# BackPlane4.net
KiCad netlist of a schematic drawn in Altium Designer
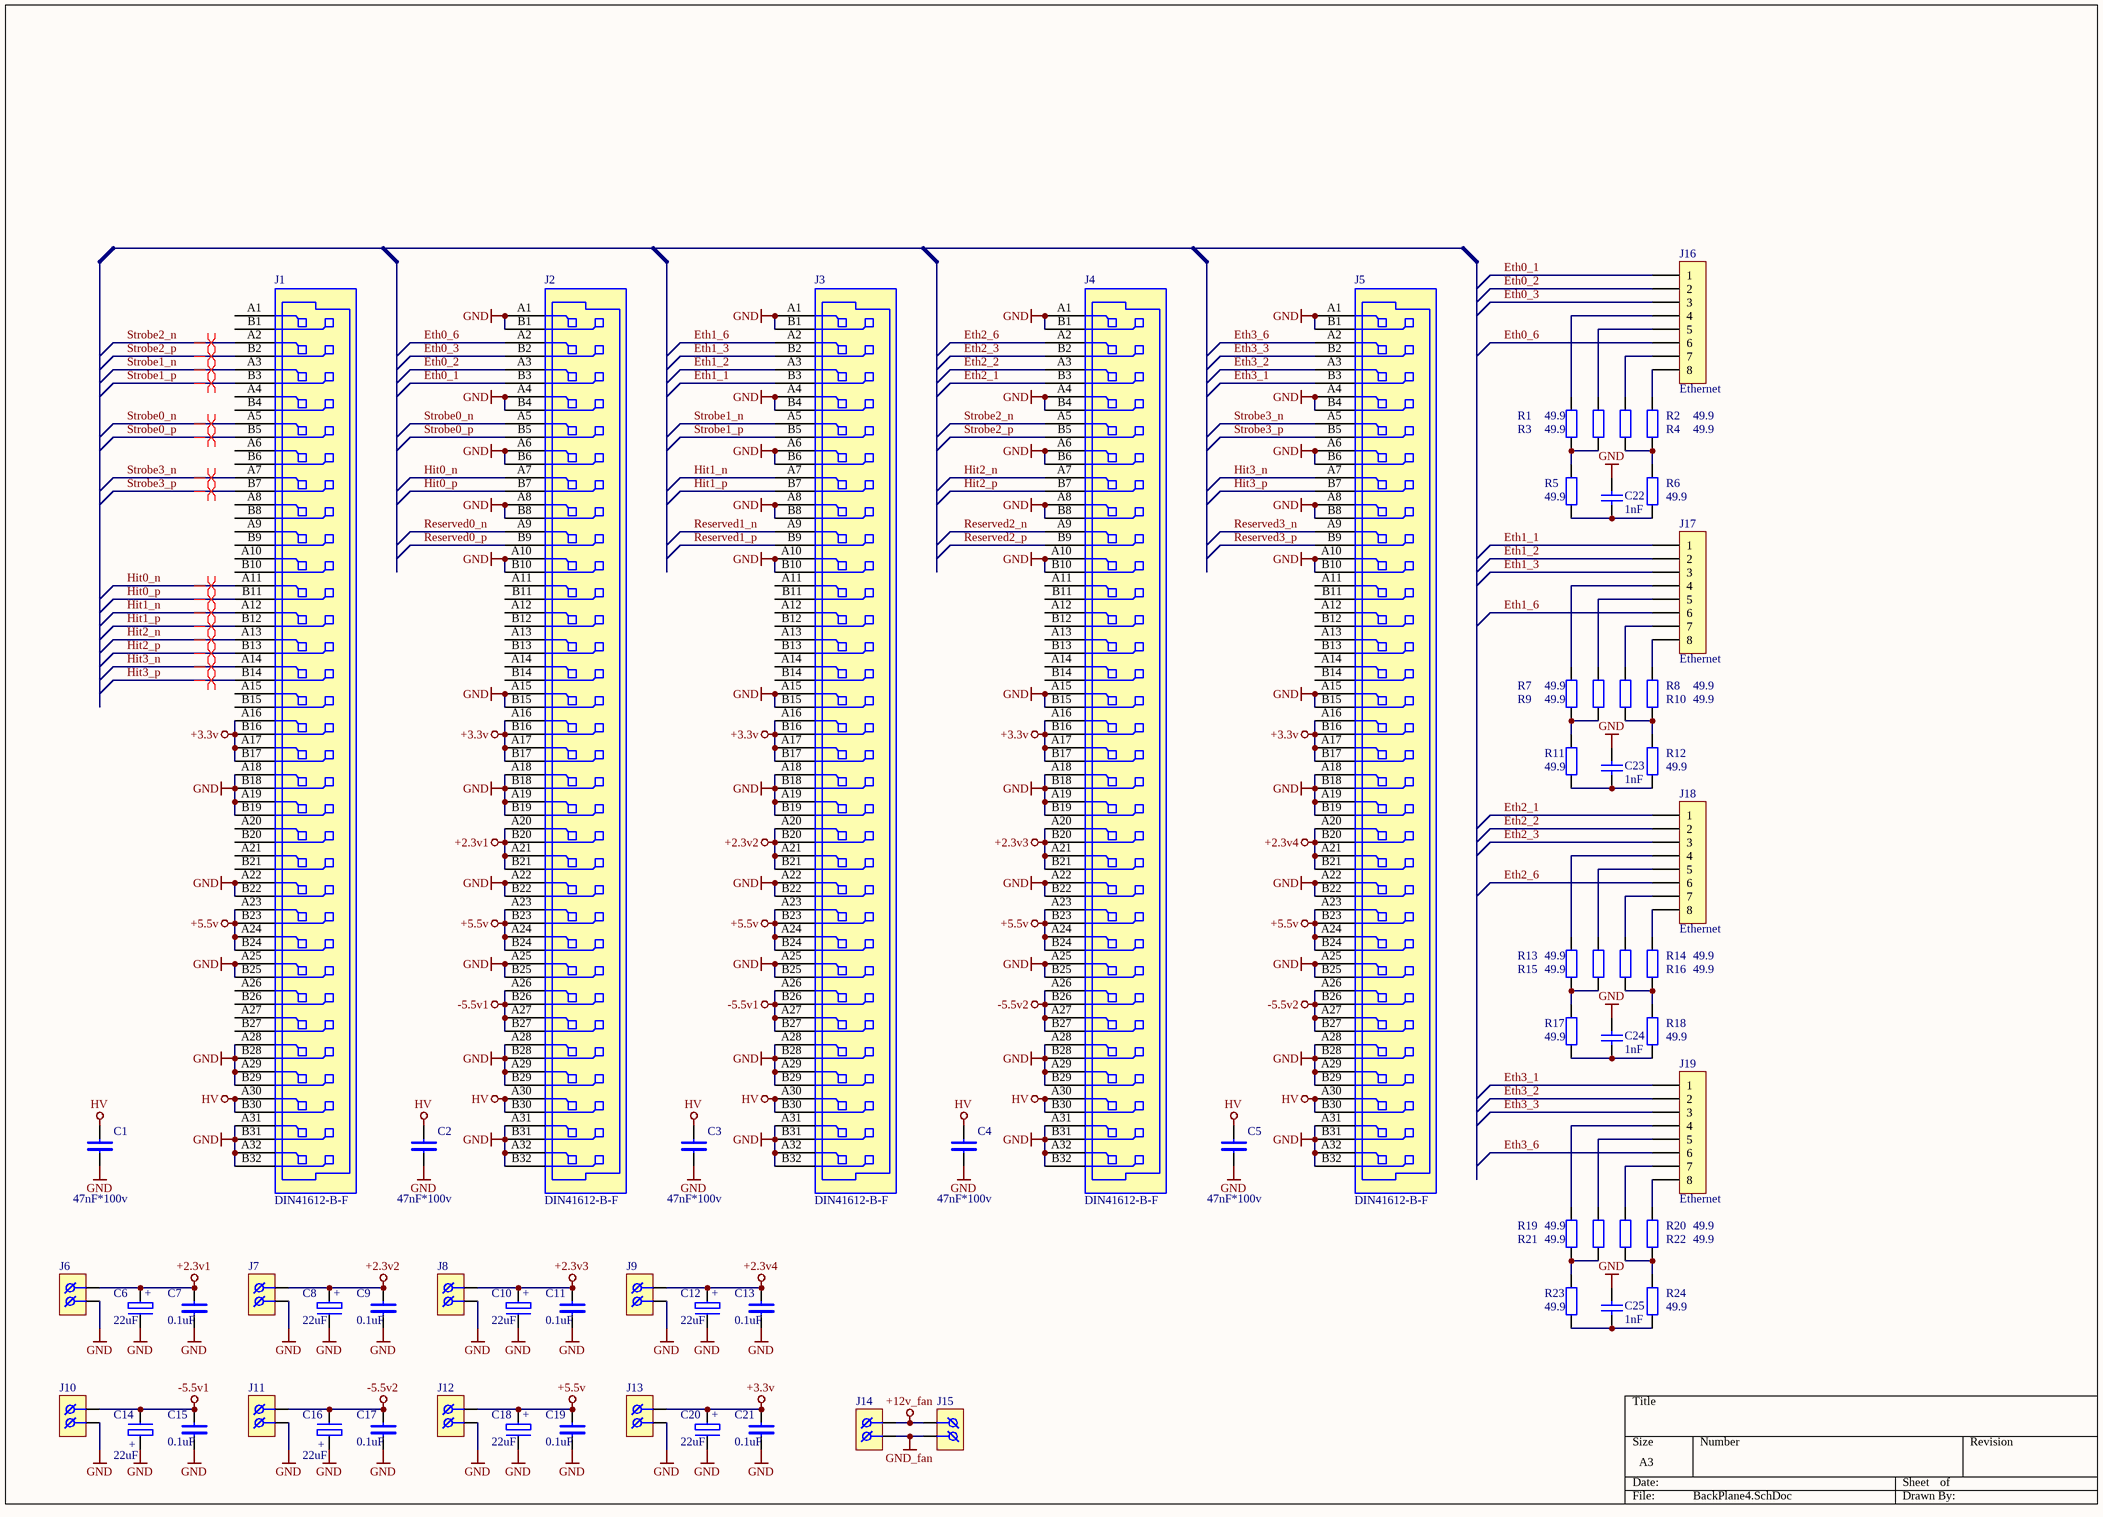
[diagram p0: BackPlane4.SchDoc]

(export (version "E")
  (design (tool "Eeschema 10.0.6"))
  (components
    (comp (ref "C1") (value "47nF*100v") (footprint "1206") (libsource (lib "*") (part "C")))
    (comp (ref "C2") (value "47nF*100v") (footprint "1206") (libsource (lib "*") (part "C")))
    (comp (ref "C3") (value "47nF*100v") (footprint "1206") (libsource (lib "*") (part "C")))
    (comp (ref "C4") (value "47nF*100v") (footprint "1206") (libsource (lib "*") (part "C")))
    (comp (ref "C5") (value "47nF*100v") (footprint "1206") (libsource (lib "*") (part "C")))
    (comp (ref "C6") (value "22uF") (footprint "CP6032") (libsource (lib "*") (part "C POL")))
    (comp (ref "C7") (value "0.1uF") (footprint "1206") (libsource (lib "*") (part "C")))
    (comp (ref "C8") (value "22uF") (footprint "CP6032") (libsource (lib "*") (part "C POL")))
    (comp (ref "C9") (value "0.1uF") (footprint "1206") (libsource (lib "*") (part "C")))
    (comp (ref "C10") (value "22uF") (footprint "CP6032") (libsource (lib "*") (part "C POL")))
    (comp (ref "C11") (value "0.1uF") (footprint "1206") (libsource (lib "*") (part "C")))
    (comp (ref "C12") (value "22uF") (footprint "CP6032") (libsource (lib "*") (part "C POL")))
    (comp (ref "C13") (value "0.1uF") (footprint "1206") (libsource (lib "*") (part "C")))
    (comp (ref "C14") (value "22uF") (footprint "CP6032") (libsource (lib "*") (part "C POL")))
    (comp (ref "C15") (value "0.1uF") (footprint "1206") (libsource (lib "*") (part "C")))
    (comp (ref "C16") (value "22uF") (footprint "CP6032") (libsource (lib "*") (part "C POL")))
    (comp (ref "C17") (value "0.1uF") (footprint "1206") (libsource (lib "*") (part "C")))
    (comp (ref "C18") (value "22uF") (footprint "CP6032") (libsource (lib "*") (part "C POL")))
    (comp (ref "C19") (value "0.1uF") (footprint "1206") (libsource (lib "*") (part "C")))
    (comp (ref "C20") (value "22uF") (footprint "CP6032") (libsource (lib "*") (part "C POL")))
    (comp (ref "C21") (value "0.1uF") (footprint "1206") (libsource (lib "*") (part "C")))
    (comp (ref "C22")
      (value "1nF")
      (footprint "0805")
      (description "Capacitor")
      (fields (field (name "PUBLISHER") "Altium Limited"))
      (libsource (lib "pcblib1") (part "Cap"))
    )
    (comp (ref "C23")
      (value "1nF")
      (footprint "0805")
      (description "Capacitor")
      (fields (field (name "PUBLISHER") "Altium Limited"))
      (libsource (lib "pcblib1") (part "Cap"))
    )
    (comp (ref "C24")
      (value "1nF")
      (footprint "0805")
      (description "Capacitor")
      (fields (field (name "PUBLISHER") "Altium Limited"))
      (libsource (lib "pcblib1") (part "Cap"))
    )
    (comp (ref "C25")
      (value "1nF")
      (footprint "0805")
      (description "Capacitor")
      (fields (field (name "PUBLISHER") "Altium Limited"))
      (libsource (lib "pcblib1") (part "Cap"))
    )
    (comp (ref "J1")
      (value "DIN41612-B-F")
      (footprint "DIN41612-B-F")
      (libsource (lib "AConnectors") (part "DIN41612-B-F"))
    )
    (comp (ref "J2")
      (value "DIN41612-B-F")
      (footprint "DIN41612-B-F")
      (libsource (lib "AConnectors") (part "DIN41612-B-F"))
    )
    (comp (ref "J3")
      (value "DIN41612-B-F")
      (footprint "DIN41612-B-F")
      (libsource (lib "AConnectors") (part "DIN41612-B-F"))
    )
    (comp (ref "J4")
      (value "DIN41612-B-F")
      (footprint "DIN41612-B-F")
      (libsource (lib "AConnectors") (part "DIN41612-B-F"))
    )
    (comp (ref "J5")
      (value "DIN41612-B-F")
      (footprint "DIN41612-B-F")
      (libsource (lib "AConnectors") (part "DIN41612-B-F"))
    )
    (comp (ref "J6")
      (value "DG300-5-02")
      (footprint "DG300-5-02")
      (libsource (lib "AConnectors") (part "DG300-5-02"))
    )
    (comp (ref "J7")
      (value "DG300-5-02")
      (footprint "DG300-5-02")
      (libsource (lib "AConnectors") (part "DG300-5-02"))
    )
    (comp (ref "J8")
      (value "DG300-5-02")
      (footprint "DG300-5-02")
      (libsource (lib "AConnectors") (part "DG300-5-02"))
    )
    (comp (ref "J9")
      (value "DG300-5-02")
      (footprint "DG300-5-02")
      (libsource (lib "AConnectors") (part "DG300-5-02"))
    )
    (comp (ref "J10")
      (value "DG300-5-02")
      (footprint "DG300-5-02")
      (libsource (lib "AConnectors") (part "DG300-5-02"))
    )
    (comp (ref "J11")
      (value "DG300-5-02")
      (footprint "DG300-5-02")
      (libsource (lib "AConnectors") (part "DG300-5-02"))
    )
    (comp (ref "J12")
      (value "DG300-5-02")
      (footprint "DG300-5-02")
      (libsource (lib "AConnectors") (part "DG300-5-02"))
    )
    (comp (ref "J13")
      (value "DG300-5-02")
      (footprint "DG300-5-02")
      (libsource (lib "AConnectors") (part "DG300-5-02"))
    )
    (comp (ref "J14")
      (value "DG300-5-02")
      (footprint "DG300-5-02")
      (libsource (lib "AConnectors") (part "DG300-5-02"))
    )
    (comp (ref "J15")
      (value "DG300-5-02")
      (footprint "DG300-5-02")
      (libsource (lib "") (part "DG300-5-02_1"))
    )
    (comp (ref "J16")
      (value "Ethernet")
      (footprint "TJ2-8P8C")
      (description "Connector")
      (libsource (lib "MyIntegratedLibrary") (part "RJ-45"))
    )
    (comp (ref "J17")
      (value "Ethernet")
      (footprint "TJ2-8P8C")
      (description "Connector")
      (libsource (lib "MyIntegratedLibrary") (part "RJ-45"))
    )
    (comp (ref "J18")
      (value "Ethernet")
      (footprint "TJ2-8P8C")
      (description "Connector")
      (libsource (lib "MyIntegratedLibrary") (part "RJ-45"))
    )
    (comp (ref "J19")
      (value "Ethernet")
      (footprint "TJ2-8P8C")
      (description "Connector")
      (libsource (lib "MyIntegratedLibrary") (part "RJ-45"))
    )
    (comp (ref "R1")
      (value "49.9")
      (footprint "0805")
      (description "Resistor")
      (fields (field (name "PUBLISHER") "Altium Limited"))
      (libsource (lib "OD3M") (part "Res2"))
    )
    (comp (ref "R2")
      (value "49.9")
      (footprint "0805")
      (description "Resistor")
      (fields (field (name "PUBLISHER") "Altium Limited"))
      (libsource (lib "OD3M") (part "Res2"))
    )
    (comp (ref "R3")
      (value "49.9")
      (footprint "0805")
      (description "Resistor")
      (fields (field (name "PUBLISHER") "Altium Limited"))
      (libsource (lib "OD3M") (part "Res2"))
    )
    (comp (ref "R4")
      (value "49.9")
      (footprint "0805")
      (description "Resistor")
      (fields (field (name "PUBLISHER") "Altium Limited"))
      (libsource (lib "OD3M") (part "Res2"))
    )
    (comp (ref "R5")
      (value "49.9")
      (footprint "0805")
      (description "Resistor")
      (fields (field (name "PUBLISHER") "Altium Limited"))
      (libsource (lib "OD3M") (part "Res2"))
    )
    (comp (ref "R6")
      (value "49.9")
      (footprint "0805")
      (description "Resistor")
      (fields (field (name "PUBLISHER") "Altium Limited"))
      (libsource (lib "OD3M") (part "Res2"))
    )
    (comp (ref "R7")
      (value "49.9")
      (footprint "0805")
      (description "Resistor")
      (fields (field (name "PUBLISHER") "Altium Limited"))
      (libsource (lib "OD3M") (part "Res2"))
    )
    (comp (ref "R8")
      (value "49.9")
      (footprint "0805")
      (description "Resistor")
      (fields (field (name "PUBLISHER") "Altium Limited"))
      (libsource (lib "OD3M") (part "Res2"))
    )
    (comp (ref "R9")
      (value "49.9")
      (footprint "0805")
      (description "Resistor")
      (fields (field (name "PUBLISHER") "Altium Limited"))
      (libsource (lib "OD3M") (part "Res2"))
    )
    (comp (ref "R10")
      (value "49.9")
      (footprint "0805")
      (description "Resistor")
      (fields (field (name "PUBLISHER") "Altium Limited"))
      (libsource (lib "OD3M") (part "Res2"))
    )
    (comp (ref "R11")
      (value "49.9")
      (footprint "0805")
      (description "Resistor")
      (fields (field (name "PUBLISHER") "Altium Limited"))
      (libsource (lib "OD3M") (part "Res2"))
    )
    (comp (ref "R12")
      (value "49.9")
      (footprint "0805")
      (description "Resistor")
      (fields (field (name "PUBLISHER") "Altium Limited"))
      (libsource (lib "OD3M") (part "Res2"))
    )
    (comp (ref "R13")
      (value "49.9")
      (footprint "0805")
      (description "Resistor")
      (fields (field (name "PUBLISHER") "Altium Limited"))
      (libsource (lib "OD3M") (part "Res2"))
    )
    (comp (ref "R14")
      (value "49.9")
      (footprint "0805")
      (description "Resistor")
      (fields (field (name "PUBLISHER") "Altium Limited"))
      (libsource (lib "OD3M") (part "Res2"))
    )
    (comp (ref "R15")
      (value "49.9")
      (footprint "0805")
      (description "Resistor")
      (fields (field (name "PUBLISHER") "Altium Limited"))
      (libsource (lib "OD3M") (part "Res2"))
    )
    (comp (ref "R16")
      (value "49.9")
      (footprint "0805")
      (description "Resistor")
      (fields (field (name "PUBLISHER") "Altium Limited"))
      (libsource (lib "OD3M") (part "Res2"))
    )
    (comp (ref "R17")
      (value "49.9")
      (footprint "0805")
      (description "Resistor")
      (fields (field (name "PUBLISHER") "Altium Limited"))
      (libsource (lib "OD3M") (part "Res2"))
    )
    (comp (ref "R18")
      (value "49.9")
      (footprint "0805")
      (description "Resistor")
      (fields (field (name "PUBLISHER") "Altium Limited"))
      (libsource (lib "OD3M") (part "Res2"))
    )
    (comp (ref "R19")
      (value "49.9")
      (footprint "0805")
      (description "Resistor")
      (fields (field (name "PUBLISHER") "Altium Limited"))
      (libsource (lib "OD3M") (part "Res2"))
    )
    (comp (ref "R20")
      (value "49.9")
      (footprint "0805")
      (description "Resistor")
      (fields (field (name "PUBLISHER") "Altium Limited"))
      (libsource (lib "OD3M") (part "Res2"))
    )
    (comp (ref "R21")
      (value "49.9")
      (footprint "0805")
      (description "Resistor")
      (fields (field (name "PUBLISHER") "Altium Limited"))
      (libsource (lib "OD3M") (part "Res2"))
    )
    (comp (ref "R22")
      (value "49.9")
      (footprint "0805")
      (description "Resistor")
      (fields (field (name "PUBLISHER") "Altium Limited"))
      (libsource (lib "OD3M") (part "Res2"))
    )
    (comp (ref "R23")
      (value "49.9")
      (footprint "0805")
      (description "Resistor")
      (fields (field (name "PUBLISHER") "Altium Limited"))
      (libsource (lib "OD3M") (part "Res2"))
    )
    (comp (ref "R24")
      (value "49.9")
      (footprint "0805")
      (description "Resistor")
      (fields (field (name "PUBLISHER") "Altium Limited"))
      (libsource (lib "OD3M") (part "Res2"))
    )
  )
  (nets
    (net (code "1") (name "+2.3v1") (class "Default")
      (node (ref "C6") (pin "+") (pinfunction "+_+") (pintype "passive"))
      (node (ref "C7") (pin "2") (pinfunction "2_2") (pintype "passive"))
      (node (ref "J2") (pin "A20") (pinfunction "A20_A20") (pintype "passive"))
      (node (ref "J2") (pin "A21") (pinfunction "A21_A21") (pintype "passive"))
      (node (ref "J2") (pin "B20") (pinfunction "B20_B20") (pintype "passive"))
      (node (ref "J2") (pin "B21") (pinfunction "B21_B21") (pintype "passive"))
      (node (ref "J6") (pin "1") (pinfunction "1_1") (pintype "passive"))
    )
    (net (code "2") (name "+2.3v2") (class "Default")
      (node (ref "C8") (pin "+") (pinfunction "+_+") (pintype "passive"))
      (node (ref "C9") (pin "2") (pinfunction "2_2") (pintype "passive"))
      (node (ref "J3") (pin "A20") (pinfunction "A20_A20") (pintype "passive"))
      (node (ref "J3") (pin "A21") (pinfunction "A21_A21") (pintype "passive"))
      (node (ref "J3") (pin "B20") (pinfunction "B20_B20") (pintype "passive"))
      (node (ref "J3") (pin "B21") (pinfunction "B21_B21") (pintype "passive"))
      (node (ref "J7") (pin "1") (pinfunction "1_1") (pintype "passive"))
    )
    (net (code "3") (name "+2.3v3") (class "Default")
      (node (ref "C10") (pin "+") (pinfunction "+_+") (pintype "passive"))
      (node (ref "C11") (pin "2") (pinfunction "2_2") (pintype "passive"))
      (node (ref "J4") (pin "A20") (pinfunction "A20_A20") (pintype "passive"))
      (node (ref "J4") (pin "A21") (pinfunction "A21_A21") (pintype "passive"))
      (node (ref "J4") (pin "B20") (pinfunction "B20_B20") (pintype "passive"))
      (node (ref "J4") (pin "B21") (pinfunction "B21_B21") (pintype "passive"))
      (node (ref "J8") (pin "1") (pinfunction "1_1") (pintype "passive"))
    )
    (net (code "4") (name "+2.3v4") (class "Default")
      (node (ref "C12") (pin "+") (pinfunction "+_+") (pintype "passive"))
      (node (ref "C13") (pin "2") (pinfunction "2_2") (pintype "passive"))
      (node (ref "J5") (pin "A20") (pinfunction "A20_A20") (pintype "passive"))
      (node (ref "J5") (pin "A21") (pinfunction "A21_A21") (pintype "passive"))
      (node (ref "J5") (pin "B20") (pinfunction "B20_B20") (pintype "passive"))
      (node (ref "J5") (pin "B21") (pinfunction "B21_B21") (pintype "passive"))
      (node (ref "J9") (pin "1") (pinfunction "1_1") (pintype "passive"))
    )
    (net (code "5") (name "+3.3v") (class "Default")
      (node (ref "C20") (pin "+") (pinfunction "+_+") (pintype "passive"))
      (node (ref "C21") (pin "2") (pinfunction "2_2") (pintype "passive"))
      (node (ref "J1") (pin "A16") (pinfunction "A16_A16") (pintype "passive"))
      (node (ref "J1") (pin "A17") (pinfunction "A17_A17") (pintype "passive"))
      (node (ref "J1") (pin "B16") (pinfunction "B16_B16") (pintype "passive"))
      (node (ref "J1") (pin "B17") (pinfunction "B17_B17") (pintype "passive"))
      (node (ref "J13") (pin "1") (pinfunction "1_1") (pintype "passive"))
      (node (ref "J2") (pin "A16") (pinfunction "A16_A16") (pintype "passive"))
      (node (ref "J2") (pin "A17") (pinfunction "A17_A17") (pintype "passive"))
      (node (ref "J2") (pin "B16") (pinfunction "B16_B16") (pintype "passive"))
      (node (ref "J2") (pin "B17") (pinfunction "B17_B17") (pintype "passive"))
      (node (ref "J3") (pin "A16") (pinfunction "A16_A16") (pintype "passive"))
      (node (ref "J3") (pin "A17") (pinfunction "A17_A17") (pintype "passive"))
      (node (ref "J3") (pin "B16") (pinfunction "B16_B16") (pintype "passive"))
      (node (ref "J3") (pin "B17") (pinfunction "B17_B17") (pintype "passive"))
      (node (ref "J4") (pin "A16") (pinfunction "A16_A16") (pintype "passive"))
      (node (ref "J4") (pin "A17") (pinfunction "A17_A17") (pintype "passive"))
      (node (ref "J4") (pin "B16") (pinfunction "B16_B16") (pintype "passive"))
      (node (ref "J4") (pin "B17") (pinfunction "B17_B17") (pintype "passive"))
      (node (ref "J5") (pin "A16") (pinfunction "A16_A16") (pintype "passive"))
      (node (ref "J5") (pin "A17") (pinfunction "A17_A17") (pintype "passive"))
      (node (ref "J5") (pin "B16") (pinfunction "B16_B16") (pintype "passive"))
      (node (ref "J5") (pin "B17") (pinfunction "B17_B17") (pintype "passive"))
    )
    (net (code "6") (name "+5.5v") (class "Default")
      (node (ref "C18") (pin "+") (pinfunction "+_+") (pintype "passive"))
      (node (ref "C19") (pin "2") (pinfunction "2_2") (pintype "passive"))
      (node (ref "J1") (pin "A23") (pinfunction "A23_A23") (pintype "passive"))
      (node (ref "J1") (pin "A24") (pinfunction "A24_A24") (pintype "passive"))
      (node (ref "J1") (pin "B23") (pinfunction "B23_B23") (pintype "passive"))
      (node (ref "J1") (pin "B24") (pinfunction "B24_B24") (pintype "passive"))
      (node (ref "J12") (pin "1") (pinfunction "1_1") (pintype "passive"))
      (node (ref "J2") (pin "A23") (pinfunction "A23_A23") (pintype "passive"))
      (node (ref "J2") (pin "A24") (pinfunction "A24_A24") (pintype "passive"))
      (node (ref "J2") (pin "B23") (pinfunction "B23_B23") (pintype "passive"))
      (node (ref "J2") (pin "B24") (pinfunction "B24_B24") (pintype "passive"))
      (node (ref "J3") (pin "A23") (pinfunction "A23_A23") (pintype "passive"))
      (node (ref "J3") (pin "A24") (pinfunction "A24_A24") (pintype "passive"))
      (node (ref "J3") (pin "B23") (pinfunction "B23_B23") (pintype "passive"))
      (node (ref "J3") (pin "B24") (pinfunction "B24_B24") (pintype "passive"))
      (node (ref "J4") (pin "A23") (pinfunction "A23_A23") (pintype "passive"))
      (node (ref "J4") (pin "A24") (pinfunction "A24_A24") (pintype "passive"))
      (node (ref "J4") (pin "B23") (pinfunction "B23_B23") (pintype "passive"))
      (node (ref "J4") (pin "B24") (pinfunction "B24_B24") (pintype "passive"))
      (node (ref "J5") (pin "A23") (pinfunction "A23_A23") (pintype "passive"))
      (node (ref "J5") (pin "A24") (pinfunction "A24_A24") (pintype "passive"))
      (node (ref "J5") (pin "B23") (pinfunction "B23_B23") (pintype "passive"))
      (node (ref "J5") (pin "B24") (pinfunction "B24_B24") (pintype "passive"))
    )
    (net (code "7") (name "+12v_fan") (class "Default")
      (node (ref "J14") (pin "1") (pinfunction "1_1") (pintype "passive"))
      (node (ref "J15") (pin "1") (pinfunction "1_1") (pintype "passive"))
    )
    (net (code "8") (name "-5.5v1") (class "Default")
      (node (ref "C14") (pin "-") (pinfunction "-_-") (pintype "passive"))
      (node (ref "C15") (pin "2") (pinfunction "2_2") (pintype "passive"))
      (node (ref "J10") (pin "1") (pinfunction "1_1") (pintype "passive"))
      (node (ref "J2") (pin "A26") (pinfunction "A26_A26") (pintype "passive"))
      (node (ref "J2") (pin "A27") (pinfunction "A27_A27") (pintype "passive"))
      (node (ref "J2") (pin "B26") (pinfunction "B26_B26") (pintype "passive"))
      (node (ref "J2") (pin "B27") (pinfunction "B27_B27") (pintype "passive"))
      (node (ref "J3") (pin "A26") (pinfunction "A26_A26") (pintype "passive"))
      (node (ref "J3") (pin "A27") (pinfunction "A27_A27") (pintype "passive"))
      (node (ref "J3") (pin "B26") (pinfunction "B26_B26") (pintype "passive"))
      (node (ref "J3") (pin "B27") (pinfunction "B27_B27") (pintype "passive"))
    )
    (net (code "9") (name "-5.5v2") (class "Default")
      (node (ref "C16") (pin "-") (pinfunction "-_-") (pintype "passive"))
      (node (ref "C17") (pin "2") (pinfunction "2_2") (pintype "passive"))
      (node (ref "J11") (pin "1") (pinfunction "1_1") (pintype "passive"))
      (node (ref "J4") (pin "A26") (pinfunction "A26_A26") (pintype "passive"))
      (node (ref "J4") (pin "A27") (pinfunction "A27_A27") (pintype "passive"))
      (node (ref "J4") (pin "B26") (pinfunction "B26_B26") (pintype "passive"))
      (node (ref "J4") (pin "B27") (pinfunction "B27_B27") (pintype "passive"))
      (node (ref "J5") (pin "A26") (pinfunction "A26_A26") (pintype "passive"))
      (node (ref "J5") (pin "A27") (pinfunction "A27_A27") (pintype "passive"))
      (node (ref "J5") (pin "B26") (pinfunction "B26_B26") (pintype "passive"))
      (node (ref "J5") (pin "B27") (pinfunction "B27_B27") (pintype "passive"))
    )
    (net (code "10") (name "/Eth0_1") (class "Default")
      (node (ref "J16") (pin "1") (pinfunction "1_1") (pintype "passive"))
      (node (ref "J2") (pin "B3") (pinfunction "B3_B3") (pintype "passive"))
    )
    (net (code "11") (name "/Eth0_2") (class "Default")
      (node (ref "J16") (pin "2") (pinfunction "2_2") (pintype "passive"))
      (node (ref "J2") (pin "A3") (pinfunction "A3_A3") (pintype "passive"))
    )
    (net (code "12") (name "/Eth0_3") (class "Default")
      (node (ref "J16") (pin "3") (pinfunction "3_3") (pintype "passive"))
      (node (ref "J2") (pin "B2") (pinfunction "B2_B2") (pintype "passive"))
    )
    (net (code "13") (name "/Eth0_6") (class "Default")
      (node (ref "J16") (pin "6") (pinfunction "6_6") (pintype "passive"))
      (node (ref "J2") (pin "A2") (pinfunction "A2_A2") (pintype "passive"))
    )
    (net (code "14") (name "/Eth1_1") (class "Default")
      (node (ref "J17") (pin "1") (pinfunction "1_1") (pintype "passive"))
      (node (ref "J3") (pin "B3") (pinfunction "B3_B3") (pintype "passive"))
    )
    (net (code "15") (name "/Eth1_2") (class "Default")
      (node (ref "J17") (pin "2") (pinfunction "2_2") (pintype "passive"))
      (node (ref "J3") (pin "A3") (pinfunction "A3_A3") (pintype "passive"))
    )
    (net (code "16") (name "/Eth1_3") (class "Default")
      (node (ref "J17") (pin "3") (pinfunction "3_3") (pintype "passive"))
      (node (ref "J3") (pin "B2") (pinfunction "B2_B2") (pintype "passive"))
    )
    (net (code "17") (name "/Eth1_6") (class "Default")
      (node (ref "J17") (pin "6") (pinfunction "6_6") (pintype "passive"))
      (node (ref "J3") (pin "A2") (pinfunction "A2_A2") (pintype "passive"))
    )
    (net (code "18") (name "/Eth2_1") (class "Default")
      (node (ref "J18") (pin "1") (pinfunction "1_1") (pintype "passive"))
      (node (ref "J4") (pin "B3") (pinfunction "B3_B3") (pintype "passive"))
    )
    (net (code "19") (name "/Eth2_2") (class "Default")
      (node (ref "J18") (pin "2") (pinfunction "2_2") (pintype "passive"))
      (node (ref "J4") (pin "A3") (pinfunction "A3_A3") (pintype "passive"))
    )
    (net (code "20") (name "/Eth2_3") (class "Default")
      (node (ref "J18") (pin "3") (pinfunction "3_3") (pintype "passive"))
      (node (ref "J4") (pin "B2") (pinfunction "B2_B2") (pintype "passive"))
    )
    (net (code "21") (name "/Eth2_6") (class "Default")
      (node (ref "J18") (pin "6") (pinfunction "6_6") (pintype "passive"))
      (node (ref "J4") (pin "A2") (pinfunction "A2_A2") (pintype "passive"))
    )
    (net (code "22") (name "/Eth3_1") (class "Default")
      (node (ref "J19") (pin "1") (pinfunction "1_1") (pintype "passive"))
      (node (ref "J5") (pin "B3") (pinfunction "B3_B3") (pintype "passive"))
    )
    (net (code "23") (name "/Eth3_2") (class "Default")
      (node (ref "J19") (pin "2") (pinfunction "2_2") (pintype "passive"))
      (node (ref "J5") (pin "A3") (pinfunction "A3_A3") (pintype "passive"))
    )
    (net (code "24") (name "/Eth3_3") (class "Default")
      (node (ref "J19") (pin "3") (pinfunction "3_3") (pintype "passive"))
      (node (ref "J5") (pin "B2") (pinfunction "B2_B2") (pintype "passive"))
    )
    (net (code "25") (name "/Eth3_6") (class "Default")
      (node (ref "J19") (pin "6") (pinfunction "6_6") (pintype "passive"))
      (node (ref "J5") (pin "A2") (pinfunction "A2_A2") (pintype "passive"))
    )
    (net (code "26") (name "/Hit0_n") (class "Default")
      (node (ref "J1") (pin "A11") (pinfunction "A11_A11") (pintype "passive"))
      (node (ref "J2") (pin "A7") (pinfunction "A7_A7") (pintype "passive"))
    )
    (net (code "27") (name "/Hit0_p") (class "Default")
      (node (ref "J1") (pin "B11") (pinfunction "B11_B11") (pintype "passive"))
      (node (ref "J2") (pin "B7") (pinfunction "B7_B7") (pintype "passive"))
    )
    (net (code "28") (name "/Hit1_n") (class "Default")
      (node (ref "J1") (pin "A12") (pinfunction "A12_A12") (pintype "passive"))
      (node (ref "J3") (pin "A7") (pinfunction "A7_A7") (pintype "passive"))
    )
    (net (code "29") (name "/Hit1_p") (class "Default")
      (node (ref "J1") (pin "B12") (pinfunction "B12_B12") (pintype "passive"))
      (node (ref "J3") (pin "B7") (pinfunction "B7_B7") (pintype "passive"))
    )
    (net (code "30") (name "/Hit2_n") (class "Default")
      (node (ref "J1") (pin "A13") (pinfunction "A13_A13") (pintype "passive"))
      (node (ref "J4") (pin "A7") (pinfunction "A7_A7") (pintype "passive"))
    )
    (net (code "31") (name "/Hit2_p") (class "Default")
      (node (ref "J1") (pin "B13") (pinfunction "B13_B13") (pintype "passive"))
      (node (ref "J4") (pin "B7") (pinfunction "B7_B7") (pintype "passive"))
    )
    (net (code "32") (name "/Hit3_n") (class "Default")
      (node (ref "J1") (pin "A14") (pinfunction "A14_A14") (pintype "passive"))
      (node (ref "J5") (pin "A7") (pinfunction "A7_A7") (pintype "passive"))
    )
    (net (code "33") (name "/Hit3_p") (class "Default")
      (node (ref "J1") (pin "B14") (pinfunction "B14_B14") (pintype "passive"))
      (node (ref "J5") (pin "B7") (pinfunction "B7_B7") (pintype "passive"))
    )
    (net (code "34") (name "/Reserved0_n") (class "Default")
      (node (ref "J2") (pin "A9") (pinfunction "A9_A9") (pintype "passive"))
    )
    (net (code "35") (name "/Reserved0_p") (class "Default")
      (node (ref "J2") (pin "B9") (pinfunction "B9_B9") (pintype "passive"))
    )
    (net (code "36") (name "/Reserved1_n") (class "Default")
      (node (ref "J3") (pin "A9") (pinfunction "A9_A9") (pintype "passive"))
    )
    (net (code "37") (name "/Reserved1_p") (class "Default")
      (node (ref "J3") (pin "B9") (pinfunction "B9_B9") (pintype "passive"))
    )
    (net (code "38") (name "/Reserved2_n") (class "Default")
      (node (ref "J4") (pin "A9") (pinfunction "A9_A9") (pintype "passive"))
    )
    (net (code "39") (name "/Reserved2_p") (class "Default")
      (node (ref "J4") (pin "B9") (pinfunction "B9_B9") (pintype "passive"))
    )
    (net (code "40") (name "/Reserved3_n") (class "Default")
      (node (ref "J5") (pin "A9") (pinfunction "A9_A9") (pintype "passive"))
    )
    (net (code "41") (name "/Reserved3_p") (class "Default")
      (node (ref "J5") (pin "B9") (pinfunction "B9_B9") (pintype "passive"))
    )
    (net (code "42") (name "/Strobe0_n") (class "Default")
      (node (ref "J1") (pin "A5") (pinfunction "A5_A5") (pintype "passive"))
      (node (ref "J2") (pin "A5") (pinfunction "A5_A5") (pintype "passive"))
    )
    (net (code "43") (name "/Strobe0_p") (class "Default")
      (node (ref "J1") (pin "B5") (pinfunction "B5_B5") (pintype "passive"))
      (node (ref "J2") (pin "B5") (pinfunction "B5_B5") (pintype "passive"))
    )
    (net (code "44") (name "/Strobe1_n") (class "Default")
      (node (ref "J1") (pin "A3") (pinfunction "A3_A3") (pintype "passive"))
      (node (ref "J3") (pin "A5") (pinfunction "A5_A5") (pintype "passive"))
    )
    (net (code "45") (name "/Strobe1_p") (class "Default")
      (node (ref "J1") (pin "B3") (pinfunction "B3_B3") (pintype "passive"))
      (node (ref "J3") (pin "B5") (pinfunction "B5_B5") (pintype "passive"))
    )
    (net (code "46") (name "/Strobe2_n") (class "Default")
      (node (ref "J1") (pin "A2") (pinfunction "A2_A2") (pintype "passive"))
      (node (ref "J4") (pin "A5") (pinfunction "A5_A5") (pintype "passive"))
    )
    (net (code "47") (name "/Strobe2_p") (class "Default")
      (node (ref "J1") (pin "B2") (pinfunction "B2_B2") (pintype "passive"))
      (node (ref "J4") (pin "B5") (pinfunction "B5_B5") (pintype "passive"))
    )
    (net (code "48") (name "/Strobe3_n") (class "Default")
      (node (ref "J1") (pin "A7") (pinfunction "A7_A7") (pintype "passive"))
      (node (ref "J5") (pin "A5") (pinfunction "A5_A5") (pintype "passive"))
    )
    (net (code "49") (name "/Strobe3_p") (class "Default")
      (node (ref "J1") (pin "B7") (pinfunction "B7_B7") (pintype "passive"))
      (node (ref "J5") (pin "B5") (pinfunction "B5_B5") (pintype "passive"))
    )
    (net (code "50") (name "GND") (class "Default")
      (node (ref "C1") (pin "1") (pinfunction "1_1") (pintype "passive"))
      (node (ref "C10") (pin "-") (pinfunction "-_-") (pintype "passive"))
      (node (ref "C11") (pin "1") (pinfunction "1_1") (pintype "passive"))
      (node (ref "C12") (pin "-") (pinfunction "-_-") (pintype "passive"))
      (node (ref "C13") (pin "1") (pinfunction "1_1") (pintype "passive"))
      (node (ref "C14") (pin "+") (pinfunction "+_+") (pintype "passive"))
      (node (ref "C15") (pin "1") (pinfunction "1_1") (pintype "passive"))
      (node (ref "C16") (pin "+") (pinfunction "+_+") (pintype "passive"))
      (node (ref "C17") (pin "1") (pinfunction "1_1") (pintype "passive"))
      (node (ref "C18") (pin "-") (pinfunction "-_-") (pintype "passive"))
      (node (ref "C19") (pin "1") (pinfunction "1_1") (pintype "passive"))
      (node (ref "C2") (pin "1") (pinfunction "1_1") (pintype "passive"))
      (node (ref "C20") (pin "-") (pinfunction "-_-") (pintype "passive"))
      (node (ref "C21") (pin "1") (pinfunction "1_1") (pintype "passive"))
      (node (ref "C22") (pin "1") (pinfunction "1_1") (pintype "passive"))
      (node (ref "C23") (pin "1") (pinfunction "1_1") (pintype "passive"))
      (node (ref "C24") (pin "1") (pinfunction "1_1") (pintype "passive"))
      (node (ref "C25") (pin "1") (pinfunction "1_1") (pintype "passive"))
      (node (ref "C3") (pin "1") (pinfunction "1_1") (pintype "passive"))
      (node (ref "C4") (pin "1") (pinfunction "1_1") (pintype "passive"))
      (node (ref "C5") (pin "1") (pinfunction "1_1") (pintype "passive"))
      (node (ref "C6") (pin "-") (pinfunction "-_-") (pintype "passive"))
      (node (ref "C7") (pin "1") (pinfunction "1_1") (pintype "passive"))
      (node (ref "C8") (pin "-") (pinfunction "-_-") (pintype "passive"))
      (node (ref "C9") (pin "1") (pinfunction "1_1") (pintype "passive"))
      (node (ref "J1") (pin "A18") (pinfunction "A18_A18") (pintype "passive"))
      (node (ref "J1") (pin "A19") (pinfunction "A19_A19") (pintype "passive"))
      (node (ref "J1") (pin "A22") (pinfunction "A22_A22") (pintype "passive"))
      (node (ref "J1") (pin "A25") (pinfunction "A25_A25") (pintype "passive"))
      (node (ref "J1") (pin "A28") (pinfunction "A28_A28") (pintype "passive"))
      (node (ref "J1") (pin "A29") (pinfunction "A29_A29") (pintype "passive"))
      (node (ref "J1") (pin "A31") (pinfunction "A31_A31") (pintype "passive"))
      (node (ref "J1") (pin "A32") (pinfunction "A32_A32") (pintype "passive"))
      (node (ref "J1") (pin "B18") (pinfunction "B18_B18") (pintype "passive"))
      (node (ref "J1") (pin "B19") (pinfunction "B19_B19") (pintype "passive"))
      (node (ref "J1") (pin "B22") (pinfunction "B22_B22") (pintype "passive"))
      (node (ref "J1") (pin "B25") (pinfunction "B25_B25") (pintype "passive"))
      (node (ref "J1") (pin "B28") (pinfunction "B28_B28") (pintype "passive"))
      (node (ref "J1") (pin "B29") (pinfunction "B29_B29") (pintype "passive"))
      (node (ref "J1") (pin "B31") (pinfunction "B31_B31") (pintype "passive"))
      (node (ref "J1") (pin "B32") (pinfunction "B32_B32") (pintype "passive"))
      (node (ref "J10") (pin "2") (pinfunction "2_2") (pintype "passive"))
      (node (ref "J11") (pin "2") (pinfunction "2_2") (pintype "passive"))
      (node (ref "J12") (pin "2") (pinfunction "2_2") (pintype "passive"))
      (node (ref "J13") (pin "2") (pinfunction "2_2") (pintype "passive"))
      (node (ref "J2") (pin "A1") (pinfunction "A1_A1") (pintype "passive"))
      (node (ref "J2") (pin "A10") (pinfunction "A10_A10") (pintype "passive"))
      (node (ref "J2") (pin "A15") (pinfunction "A15_A15") (pintype "passive"))
      (node (ref "J2") (pin "A18") (pinfunction "A18_A18") (pintype "passive"))
      (node (ref "J2") (pin "A19") (pinfunction "A19_A19") (pintype "passive"))
      (node (ref "J2") (pin "A22") (pinfunction "A22_A22") (pintype "passive"))
      (node (ref "J2") (pin "A25") (pinfunction "A25_A25") (pintype "passive"))
      (node (ref "J2") (pin "A28") (pinfunction "A28_A28") (pintype "passive"))
      (node (ref "J2") (pin "A29") (pinfunction "A29_A29") (pintype "passive"))
      (node (ref "J2") (pin "A31") (pinfunction "A31_A31") (pintype "passive"))
      (node (ref "J2") (pin "A32") (pinfunction "A32_A32") (pintype "passive"))
      (node (ref "J2") (pin "A4") (pinfunction "A4_A4") (pintype "passive"))
      (node (ref "J2") (pin "A6") (pinfunction "A6_A6") (pintype "passive"))
      (node (ref "J2") (pin "A8") (pinfunction "A8_A8") (pintype "passive"))
      (node (ref "J2") (pin "B1") (pinfunction "B1_B1") (pintype "passive"))
      (node (ref "J2") (pin "B10") (pinfunction "B10_B10") (pintype "passive"))
      (node (ref "J2") (pin "B15") (pinfunction "B15_B15") (pintype "passive"))
      (node (ref "J2") (pin "B18") (pinfunction "B18_B18") (pintype "passive"))
      (node (ref "J2") (pin "B19") (pinfunction "B19_B19") (pintype "passive"))
      (node (ref "J2") (pin "B22") (pinfunction "B22_B22") (pintype "passive"))
      (node (ref "J2") (pin "B25") (pinfunction "B25_B25") (pintype "passive"))
      (node (ref "J2") (pin "B28") (pinfunction "B28_B28") (pintype "passive"))
      (node (ref "J2") (pin "B29") (pinfunction "B29_B29") (pintype "passive"))
      (node (ref "J2") (pin "B31") (pinfunction "B31_B31") (pintype "passive"))
      (node (ref "J2") (pin "B32") (pinfunction "B32_B32") (pintype "passive"))
      (node (ref "J2") (pin "B4") (pinfunction "B4_B4") (pintype "passive"))
      (node (ref "J2") (pin "B6") (pinfunction "B6_B6") (pintype "passive"))
      (node (ref "J2") (pin "B8") (pinfunction "B8_B8") (pintype "passive"))
      (node (ref "J3") (pin "A1") (pinfunction "A1_A1") (pintype "passive"))
      (node (ref "J3") (pin "A10") (pinfunction "A10_A10") (pintype "passive"))
      (node (ref "J3") (pin "A15") (pinfunction "A15_A15") (pintype "passive"))
      (node (ref "J3") (pin "A18") (pinfunction "A18_A18") (pintype "passive"))
      (node (ref "J3") (pin "A19") (pinfunction "A19_A19") (pintype "passive"))
      (node (ref "J3") (pin "A22") (pinfunction "A22_A22") (pintype "passive"))
      (node (ref "J3") (pin "A25") (pinfunction "A25_A25") (pintype "passive"))
      (node (ref "J3") (pin "A28") (pinfunction "A28_A28") (pintype "passive"))
      (node (ref "J3") (pin "A29") (pinfunction "A29_A29") (pintype "passive"))
      (node (ref "J3") (pin "A31") (pinfunction "A31_A31") (pintype "passive"))
      (node (ref "J3") (pin "A32") (pinfunction "A32_A32") (pintype "passive"))
      (node (ref "J3") (pin "A4") (pinfunction "A4_A4") (pintype "passive"))
      (node (ref "J3") (pin "A6") (pinfunction "A6_A6") (pintype "passive"))
      (node (ref "J3") (pin "A8") (pinfunction "A8_A8") (pintype "passive"))
      (node (ref "J3") (pin "B1") (pinfunction "B1_B1") (pintype "passive"))
      (node (ref "J3") (pin "B10") (pinfunction "B10_B10") (pintype "passive"))
      (node (ref "J3") (pin "B15") (pinfunction "B15_B15") (pintype "passive"))
      (node (ref "J3") (pin "B18") (pinfunction "B18_B18") (pintype "passive"))
      (node (ref "J3") (pin "B19") (pinfunction "B19_B19") (pintype "passive"))
      (node (ref "J3") (pin "B22") (pinfunction "B22_B22") (pintype "passive"))
      (node (ref "J3") (pin "B25") (pinfunction "B25_B25") (pintype "passive"))
      (node (ref "J3") (pin "B28") (pinfunction "B28_B28") (pintype "passive"))
      (node (ref "J3") (pin "B29") (pinfunction "B29_B29") (pintype "passive"))
      (node (ref "J3") (pin "B31") (pinfunction "B31_B31") (pintype "passive"))
      (node (ref "J3") (pin "B32") (pinfunction "B32_B32") (pintype "passive"))
      (node (ref "J3") (pin "B4") (pinfunction "B4_B4") (pintype "passive"))
      (node (ref "J3") (pin "B6") (pinfunction "B6_B6") (pintype "passive"))
      (node (ref "J3") (pin "B8") (pinfunction "B8_B8") (pintype "passive"))
      (node (ref "J4") (pin "A1") (pinfunction "A1_A1") (pintype "passive"))
      (node (ref "J4") (pin "A10") (pinfunction "A10_A10") (pintype "passive"))
      (node (ref "J4") (pin "A15") (pinfunction "A15_A15") (pintype "passive"))
      (node (ref "J4") (pin "A18") (pinfunction "A18_A18") (pintype "passive"))
      (node (ref "J4") (pin "A19") (pinfunction "A19_A19") (pintype "passive"))
      (node (ref "J4") (pin "A22") (pinfunction "A22_A22") (pintype "passive"))
      (node (ref "J4") (pin "A25") (pinfunction "A25_A25") (pintype "passive"))
      (node (ref "J4") (pin "A28") (pinfunction "A28_A28") (pintype "passive"))
      (node (ref "J4") (pin "A29") (pinfunction "A29_A29") (pintype "passive"))
      (node (ref "J4") (pin "A31") (pinfunction "A31_A31") (pintype "passive"))
      (node (ref "J4") (pin "A32") (pinfunction "A32_A32") (pintype "passive"))
      (node (ref "J4") (pin "A4") (pinfunction "A4_A4") (pintype "passive"))
      (node (ref "J4") (pin "A6") (pinfunction "A6_A6") (pintype "passive"))
      (node (ref "J4") (pin "A8") (pinfunction "A8_A8") (pintype "passive"))
      (node (ref "J4") (pin "B1") (pinfunction "B1_B1") (pintype "passive"))
      (node (ref "J4") (pin "B10") (pinfunction "B10_B10") (pintype "passive"))
      (node (ref "J4") (pin "B15") (pinfunction "B15_B15") (pintype "passive"))
      (node (ref "J4") (pin "B18") (pinfunction "B18_B18") (pintype "passive"))
      (node (ref "J4") (pin "B19") (pinfunction "B19_B19") (pintype "passive"))
      (node (ref "J4") (pin "B22") (pinfunction "B22_B22") (pintype "passive"))
      (node (ref "J4") (pin "B25") (pinfunction "B25_B25") (pintype "passive"))
      (node (ref "J4") (pin "B28") (pinfunction "B28_B28") (pintype "passive"))
      (node (ref "J4") (pin "B29") (pinfunction "B29_B29") (pintype "passive"))
      (node (ref "J4") (pin "B31") (pinfunction "B31_B31") (pintype "passive"))
      (node (ref "J4") (pin "B32") (pinfunction "B32_B32") (pintype "passive"))
      (node (ref "J4") (pin "B4") (pinfunction "B4_B4") (pintype "passive"))
      (node (ref "J4") (pin "B6") (pinfunction "B6_B6") (pintype "passive"))
      (node (ref "J4") (pin "B8") (pinfunction "B8_B8") (pintype "passive"))
      (node (ref "J5") (pin "A1") (pinfunction "A1_A1") (pintype "passive"))
      (node (ref "J5") (pin "A10") (pinfunction "A10_A10") (pintype "passive"))
      (node (ref "J5") (pin "A15") (pinfunction "A15_A15") (pintype "passive"))
      (node (ref "J5") (pin "A18") (pinfunction "A18_A18") (pintype "passive"))
      (node (ref "J5") (pin "A19") (pinfunction "A19_A19") (pintype "passive"))
      (node (ref "J5") (pin "A22") (pinfunction "A22_A22") (pintype "passive"))
      (node (ref "J5") (pin "A25") (pinfunction "A25_A25") (pintype "passive"))
      (node (ref "J5") (pin "A28") (pinfunction "A28_A28") (pintype "passive"))
      (node (ref "J5") (pin "A29") (pinfunction "A29_A29") (pintype "passive"))
      (node (ref "J5") (pin "A31") (pinfunction "A31_A31") (pintype "passive"))
      (node (ref "J5") (pin "A32") (pinfunction "A32_A32") (pintype "passive"))
      (node (ref "J5") (pin "A4") (pinfunction "A4_A4") (pintype "passive"))
      (node (ref "J5") (pin "A6") (pinfunction "A6_A6") (pintype "passive"))
      (node (ref "J5") (pin "A8") (pinfunction "A8_A8") (pintype "passive"))
      (node (ref "J5") (pin "B1") (pinfunction "B1_B1") (pintype "passive"))
      (node (ref "J5") (pin "B10") (pinfunction "B10_B10") (pintype "passive"))
      (node (ref "J5") (pin "B15") (pinfunction "B15_B15") (pintype "passive"))
      (node (ref "J5") (pin "B18") (pinfunction "B18_B18") (pintype "passive"))
      (node (ref "J5") (pin "B19") (pinfunction "B19_B19") (pintype "passive"))
      (node (ref "J5") (pin "B22") (pinfunction "B22_B22") (pintype "passive"))
      (node (ref "J5") (pin "B25") (pinfunction "B25_B25") (pintype "passive"))
      (node (ref "J5") (pin "B28") (pinfunction "B28_B28") (pintype "passive"))
      (node (ref "J5") (pin "B29") (pinfunction "B29_B29") (pintype "passive"))
      (node (ref "J5") (pin "B31") (pinfunction "B31_B31") (pintype "passive"))
      (node (ref "J5") (pin "B32") (pinfunction "B32_B32") (pintype "passive"))
      (node (ref "J5") (pin "B4") (pinfunction "B4_B4") (pintype "passive"))
      (node (ref "J5") (pin "B6") (pinfunction "B6_B6") (pintype "passive"))
      (node (ref "J5") (pin "B8") (pinfunction "B8_B8") (pintype "passive"))
      (node (ref "J6") (pin "2") (pinfunction "2_2") (pintype "passive"))
      (node (ref "J7") (pin "2") (pinfunction "2_2") (pintype "passive"))
      (node (ref "J8") (pin "2") (pinfunction "2_2") (pintype "passive"))
      (node (ref "J9") (pin "2") (pinfunction "2_2") (pintype "passive"))
    )
    (net (code "51") (name "GND_fan") (class "Default")
      (node (ref "J14") (pin "2") (pinfunction "2_2") (pintype "passive"))
      (node (ref "J15") (pin "2") (pinfunction "2_2") (pintype "passive"))
    )
    (net (code "52") (name "HV") (class "Default")
      (node (ref "C1") (pin "2") (pinfunction "2_2") (pintype "passive"))
      (node (ref "C2") (pin "2") (pinfunction "2_2") (pintype "passive"))
      (node (ref "C3") (pin "2") (pinfunction "2_2") (pintype "passive"))
      (node (ref "C4") (pin "2") (pinfunction "2_2") (pintype "passive"))
      (node (ref "C5") (pin "2") (pinfunction "2_2") (pintype "passive"))
      (node (ref "J1") (pin "A30") (pinfunction "A30_A30") (pintype "passive"))
      (node (ref "J1") (pin "B30") (pinfunction "B30_B30") (pintype "passive"))
      (node (ref "J2") (pin "A30") (pinfunction "A30_A30") (pintype "passive"))
      (node (ref "J2") (pin "B30") (pinfunction "B30_B30") (pintype "passive"))
      (node (ref "J3") (pin "A30") (pinfunction "A30_A30") (pintype "passive"))
      (node (ref "J3") (pin "B30") (pinfunction "B30_B30") (pintype "passive"))
      (node (ref "J4") (pin "A30") (pinfunction "A30_A30") (pintype "passive"))
      (node (ref "J4") (pin "B30") (pinfunction "B30_B30") (pintype "passive"))
      (node (ref "J5") (pin "A30") (pinfunction "A30_A30") (pintype "passive"))
      (node (ref "J5") (pin "B30") (pinfunction "B30_B30") (pintype "passive"))
    )
    (net (code "53") (name "Net-(C22-Pad2)") (class "Default")
      (node (ref "C22") (pin "2") (pinfunction "2_2") (pintype "passive"))
      (node (ref "R5") (pin "2") (pinfunction "2_2") (pintype "passive"))
      (node (ref "R6") (pin "2") (pinfunction "2_2") (pintype "passive"))
    )
    (net (code "54") (name "Net-(C23-Pad2)") (class "Default")
      (node (ref "C23") (pin "2") (pinfunction "2_2") (pintype "passive"))
      (node (ref "R11") (pin "2") (pinfunction "2_2") (pintype "passive"))
      (node (ref "R12") (pin "2") (pinfunction "2_2") (pintype "passive"))
    )
    (net (code "55") (name "Net-(C24-Pad2)") (class "Default")
      (node (ref "C24") (pin "2") (pinfunction "2_2") (pintype "passive"))
      (node (ref "R17") (pin "2") (pinfunction "2_2") (pintype "passive"))
      (node (ref "R18") (pin "2") (pinfunction "2_2") (pintype "passive"))
    )
    (net (code "56") (name "Net-(C25-Pad2)") (class "Default")
      (node (ref "C25") (pin "2") (pinfunction "2_2") (pintype "passive"))
      (node (ref "R23") (pin "2") (pinfunction "2_2") (pintype "passive"))
      (node (ref "R24") (pin "2") (pinfunction "2_2") (pintype "passive"))
    )
    (net (code "57") (name "Net-(J16-Pad4)") (class "Default")
      (node (ref "J16") (pin "4") (pinfunction "4_4") (pintype "passive"))
      (node (ref "R1") (pin "1") (pinfunction "1_1") (pintype "passive"))
    )
    (net (code "58") (name "Net-(J16-Pad5)") (class "Default")
      (node (ref "J16") (pin "5") (pinfunction "5_5") (pintype "passive"))
      (node (ref "R3") (pin "1") (pinfunction "1_1") (pintype "passive"))
    )
    (net (code "59") (name "Net-(J16-Pad7)") (class "Default")
      (node (ref "J16") (pin "7") (pinfunction "7_7") (pintype "passive"))
      (node (ref "R4") (pin "1") (pinfunction "1_1") (pintype "passive"))
    )
    (net (code "60") (name "Net-(J16-Pad8)") (class "Default")
      (node (ref "J16") (pin "8") (pinfunction "8_8") (pintype "passive"))
      (node (ref "R2") (pin "1") (pinfunction "1_1") (pintype "passive"))
    )
    (net (code "61") (name "Net-(J17-Pad4)") (class "Default")
      (node (ref "J17") (pin "4") (pinfunction "4_4") (pintype "passive"))
      (node (ref "R7") (pin "1") (pinfunction "1_1") (pintype "passive"))
    )
    (net (code "62") (name "Net-(J17-Pad5)") (class "Default")
      (node (ref "J17") (pin "5") (pinfunction "5_5") (pintype "passive"))
      (node (ref "R9") (pin "1") (pinfunction "1_1") (pintype "passive"))
    )
    (net (code "63") (name "Net-(J17-Pad7)") (class "Default")
      (node (ref "J17") (pin "7") (pinfunction "7_7") (pintype "passive"))
      (node (ref "R10") (pin "1") (pinfunction "1_1") (pintype "passive"))
    )
    (net (code "64") (name "Net-(J17-Pad8)") (class "Default")
      (node (ref "J17") (pin "8") (pinfunction "8_8") (pintype "passive"))
      (node (ref "R8") (pin "1") (pinfunction "1_1") (pintype "passive"))
    )
    (net (code "65") (name "Net-(J18-Pad4)") (class "Default")
      (node (ref "J18") (pin "4") (pinfunction "4_4") (pintype "passive"))
      (node (ref "R13") (pin "1") (pinfunction "1_1") (pintype "passive"))
    )
    (net (code "66") (name "Net-(J18-Pad5)") (class "Default")
      (node (ref "J18") (pin "5") (pinfunction "5_5") (pintype "passive"))
      (node (ref "R15") (pin "1") (pinfunction "1_1") (pintype "passive"))
    )
    (net (code "67") (name "Net-(J18-Pad7)") (class "Default")
      (node (ref "J18") (pin "7") (pinfunction "7_7") (pintype "passive"))
      (node (ref "R16") (pin "1") (pinfunction "1_1") (pintype "passive"))
    )
    (net (code "68") (name "Net-(J18-Pad8)") (class "Default")
      (node (ref "J18") (pin "8") (pinfunction "8_8") (pintype "passive"))
      (node (ref "R14") (pin "1") (pinfunction "1_1") (pintype "passive"))
    )
    (net (code "69") (name "Net-(J19-Pad4)") (class "Default")
      (node (ref "J19") (pin "4") (pinfunction "4_4") (pintype "passive"))
      (node (ref "R19") (pin "1") (pinfunction "1_1") (pintype "passive"))
    )
    (net (code "70") (name "Net-(J19-Pad5)") (class "Default")
      (node (ref "J19") (pin "5") (pinfunction "5_5") (pintype "passive"))
      (node (ref "R21") (pin "1") (pinfunction "1_1") (pintype "passive"))
    )
    (net (code "71") (name "Net-(J19-Pad7)") (class "Default")
      (node (ref "J19") (pin "7") (pinfunction "7_7") (pintype "passive"))
      (node (ref "R22") (pin "1") (pinfunction "1_1") (pintype "passive"))
    )
    (net (code "72") (name "Net-(J19-Pad8)") (class "Default")
      (node (ref "J19") (pin "8") (pinfunction "8_8") (pintype "passive"))
      (node (ref "R20") (pin "1") (pinfunction "1_1") (pintype "passive"))
    )
    (net (code "73") (name "Net-(R1-Pad2)") (class "Default")
      (node (ref "R1") (pin "2") (pinfunction "2_2") (pintype "passive"))
      (node (ref "R3") (pin "2") (pinfunction "2_2") (pintype "passive"))
      (node (ref "R5") (pin "1") (pinfunction "1_1") (pintype "passive"))
    )
    (net (code "74") (name "Net-(R2-Pad2)") (class "Default")
      (node (ref "R2") (pin "2") (pinfunction "2_2") (pintype "passive"))
      (node (ref "R4") (pin "2") (pinfunction "2_2") (pintype "passive"))
      (node (ref "R6") (pin "1") (pinfunction "1_1") (pintype "passive"))
    )
    (net (code "75") (name "Net-(R10-Pad2)") (class "Default")
      (node (ref "R10") (pin "2") (pinfunction "2_2") (pintype "passive"))
      (node (ref "R12") (pin "1") (pinfunction "1_1") (pintype "passive"))
      (node (ref "R8") (pin "2") (pinfunction "2_2") (pintype "passive"))
    )
    (net (code "76") (name "Net-(R11-Pad1)") (class "Default")
      (node (ref "R11") (pin "1") (pinfunction "1_1") (pintype "passive"))
      (node (ref "R7") (pin "2") (pinfunction "2_2") (pintype "passive"))
      (node (ref "R9") (pin "2") (pinfunction "2_2") (pintype "passive"))
    )
    (net (code "77") (name "Net-(R13-Pad2)") (class "Default")
      (node (ref "R13") (pin "2") (pinfunction "2_2") (pintype "passive"))
      (node (ref "R15") (pin "2") (pinfunction "2_2") (pintype "passive"))
      (node (ref "R17") (pin "1") (pinfunction "1_1") (pintype "passive"))
    )
    (net (code "78") (name "Net-(R14-Pad2)") (class "Default")
      (node (ref "R14") (pin "2") (pinfunction "2_2") (pintype "passive"))
      (node (ref "R16") (pin "2") (pinfunction "2_2") (pintype "passive"))
      (node (ref "R18") (pin "1") (pinfunction "1_1") (pintype "passive"))
    )
    (net (code "79") (name "Net-(R19-Pad2)") (class "Default")
      (node (ref "R19") (pin "2") (pinfunction "2_2") (pintype "passive"))
      (node (ref "R21") (pin "2") (pinfunction "2_2") (pintype "passive"))
      (node (ref "R23") (pin "1") (pinfunction "1_1") (pintype "passive"))
    )
    (net (code "80") (name "Net-(R20-Pad2)") (class "Default")
      (node (ref "R20") (pin "2") (pinfunction "2_2") (pintype "passive"))
      (node (ref "R22") (pin "2") (pinfunction "2_2") (pintype "passive"))
      (node (ref "R24") (pin "1") (pinfunction "1_1") (pintype "passive"))
    )
    (net (code "81") (name "unconnected-(J1-PadA1)") (class "Default")
      (node (ref "J1") (pin "A1") (pinfunction "A1_A1") (pintype "passive"))
    )
    (net (code "82") (name "unconnected-(J1-PadA4)") (class "Default")
      (node (ref "J1") (pin "A4") (pinfunction "A4_A4") (pintype "passive"))
    )
    (net (code "83") (name "unconnected-(J1-PadA6)") (class "Default")
      (node (ref "J1") (pin "A6") (pinfunction "A6_A6") (pintype "passive"))
    )
    (net (code "84") (name "unconnected-(J1-PadA8)") (class "Default")
      (node (ref "J1") (pin "A8") (pinfunction "A8_A8") (pintype "passive"))
    )
    (net (code "85") (name "unconnected-(J1-PadA9)") (class "Default")
      (node (ref "J1") (pin "A9") (pinfunction "A9_A9") (pintype "passive"))
    )
    (net (code "86") (name "unconnected-(J1-PadA10)") (class "Default")
      (node (ref "J1") (pin "A10") (pinfunction "A10_A10") (pintype "passive"))
    )
    (net (code "87") (name "unconnected-(J1-PadA15)") (class "Default")
      (node (ref "J1") (pin "A15") (pinfunction "A15_A15") (pintype "passive"))
    )
    (net (code "88") (name "unconnected-(J1-PadA20)") (class "Default")
      (node (ref "J1") (pin "A20") (pinfunction "A20_A20") (pintype "passive"))
    )
    (net (code "89") (name "unconnected-(J1-PadA21)") (class "Default")
      (node (ref "J1") (pin "A21") (pinfunction "A21_A21") (pintype "passive"))
    )
    (net (code "90") (name "unconnected-(J1-PadA26)") (class "Default")
      (node (ref "J1") (pin "A26") (pinfunction "A26_A26") (pintype "passive"))
    )
    (net (code "91") (name "unconnected-(J1-PadA27)") (class "Default")
      (node (ref "J1") (pin "A27") (pinfunction "A27_A27") (pintype "passive"))
    )
    (net (code "92") (name "unconnected-(J1-PadB1)") (class "Default")
      (node (ref "J1") (pin "B1") (pinfunction "B1_B1") (pintype "passive"))
    )
    (net (code "93") (name "unconnected-(J1-PadB4)") (class "Default")
      (node (ref "J1") (pin "B4") (pinfunction "B4_B4") (pintype "passive"))
    )
    (net (code "94") (name "unconnected-(J1-PadB6)") (class "Default")
      (node (ref "J1") (pin "B6") (pinfunction "B6_B6") (pintype "passive"))
    )
    (net (code "95") (name "unconnected-(J1-PadB8)") (class "Default")
      (node (ref "J1") (pin "B8") (pinfunction "B8_B8") (pintype "passive"))
    )
    (net (code "96") (name "unconnected-(J1-PadB9)") (class "Default")
      (node (ref "J1") (pin "B9") (pinfunction "B9_B9") (pintype "passive"))
    )
    (net (code "97") (name "unconnected-(J1-PadB10)") (class "Default")
      (node (ref "J1") (pin "B10") (pinfunction "B10_B10") (pintype "passive"))
    )
    (net (code "98") (name "unconnected-(J1-PadB15)") (class "Default")
      (node (ref "J1") (pin "B15") (pinfunction "B15_B15") (pintype "passive"))
    )
    (net (code "99") (name "unconnected-(J1-PadB20)") (class "Default")
      (node (ref "J1") (pin "B20") (pinfunction "B20_B20") (pintype "passive"))
    )
    (net (code "100") (name "unconnected-(J1-PadB21)") (class "Default")
      (node (ref "J1") (pin "B21") (pinfunction "B21_B21") (pintype "passive"))
    )
    (net (code "101") (name "unconnected-(J1-PadB26)") (class "Default")
      (node (ref "J1") (pin "B26") (pinfunction "B26_B26") (pintype "passive"))
    )
    (net (code "102") (name "unconnected-(J1-PadB27)") (class "Default")
      (node (ref "J1") (pin "B27") (pinfunction "B27_B27") (pintype "passive"))
    )
    (net (code "103") (name "unconnected-(J2-PadA11)") (class "Default")
      (node (ref "J2") (pin "A11") (pinfunction "A11_A11") (pintype "passive"))
    )
    (net (code "104") (name "unconnected-(J2-PadA12)") (class "Default")
      (node (ref "J2") (pin "A12") (pinfunction "A12_A12") (pintype "passive"))
    )
    (net (code "105") (name "unconnected-(J2-PadA13)") (class "Default")
      (node (ref "J2") (pin "A13") (pinfunction "A13_A13") (pintype "passive"))
    )
    (net (code "106") (name "unconnected-(J2-PadA14)") (class "Default")
      (node (ref "J2") (pin "A14") (pinfunction "A14_A14") (pintype "passive"))
    )
    (net (code "107") (name "unconnected-(J2-PadB11)") (class "Default")
      (node (ref "J2") (pin "B11") (pinfunction "B11_B11") (pintype "passive"))
    )
    (net (code "108") (name "unconnected-(J2-PadB12)") (class "Default")
      (node (ref "J2") (pin "B12") (pinfunction "B12_B12") (pintype "passive"))
    )
    (net (code "109") (name "unconnected-(J2-PadB13)") (class "Default")
      (node (ref "J2") (pin "B13") (pinfunction "B13_B13") (pintype "passive"))
    )
    (net (code "110") (name "unconnected-(J2-PadB14)") (class "Default")
      (node (ref "J2") (pin "B14") (pinfunction "B14_B14") (pintype "passive"))
    )
    (net (code "111") (name "unconnected-(J3-PadA11)") (class "Default")
      (node (ref "J3") (pin "A11") (pinfunction "A11_A11") (pintype "passive"))
    )
    (net (code "112") (name "unconnected-(J3-PadA12)") (class "Default")
      (node (ref "J3") (pin "A12") (pinfunction "A12_A12") (pintype "passive"))
    )
    (net (code "113") (name "unconnected-(J3-PadA13)") (class "Default")
      (node (ref "J3") (pin "A13") (pinfunction "A13_A13") (pintype "passive"))
    )
    (net (code "114") (name "unconnected-(J3-PadA14)") (class "Default")
      (node (ref "J3") (pin "A14") (pinfunction "A14_A14") (pintype "passive"))
    )
    (net (code "115") (name "unconnected-(J3-PadB11)") (class "Default")
      (node (ref "J3") (pin "B11") (pinfunction "B11_B11") (pintype "passive"))
    )
    (net (code "116") (name "unconnected-(J3-PadB12)") (class "Default")
      (node (ref "J3") (pin "B12") (pinfunction "B12_B12") (pintype "passive"))
    )
    (net (code "117") (name "unconnected-(J3-PadB13)") (class "Default")
      (node (ref "J3") (pin "B13") (pinfunction "B13_B13") (pintype "passive"))
    )
    (net (code "118") (name "unconnected-(J3-PadB14)") (class "Default")
      (node (ref "J3") (pin "B14") (pinfunction "B14_B14") (pintype "passive"))
    )
    (net (code "119") (name "unconnected-(J4-PadA11)") (class "Default")
      (node (ref "J4") (pin "A11") (pinfunction "A11_A11") (pintype "passive"))
    )
    (net (code "120") (name "unconnected-(J4-PadA12)") (class "Default")
      (node (ref "J4") (pin "A12") (pinfunction "A12_A12") (pintype "passive"))
    )
    (net (code "121") (name "unconnected-(J4-PadA13)") (class "Default")
      (node (ref "J4") (pin "A13") (pinfunction "A13_A13") (pintype "passive"))
    )
    (net (code "122") (name "unconnected-(J4-PadA14)") (class "Default")
      (node (ref "J4") (pin "A14") (pinfunction "A14_A14") (pintype "passive"))
    )
    (net (code "123") (name "unconnected-(J4-PadB11)") (class "Default")
      (node (ref "J4") (pin "B11") (pinfunction "B11_B11") (pintype "passive"))
    )
    (net (code "124") (name "unconnected-(J4-PadB12)") (class "Default")
      (node (ref "J4") (pin "B12") (pinfunction "B12_B12") (pintype "passive"))
    )
    (net (code "125") (name "unconnected-(J4-PadB13)") (class "Default")
      (node (ref "J4") (pin "B13") (pinfunction "B13_B13") (pintype "passive"))
    )
    (net (code "126") (name "unconnected-(J4-PadB14)") (class "Default")
      (node (ref "J4") (pin "B14") (pinfunction "B14_B14") (pintype "passive"))
    )
    (net (code "127") (name "unconnected-(J5-PadA11)") (class "Default")
      (node (ref "J5") (pin "A11") (pinfunction "A11_A11") (pintype "passive"))
    )
    (net (code "128") (name "unconnected-(J5-PadA12)") (class "Default")
      (node (ref "J5") (pin "A12") (pinfunction "A12_A12") (pintype "passive"))
    )
    (net (code "129") (name "unconnected-(J5-PadA13)") (class "Default")
      (node (ref "J5") (pin "A13") (pinfunction "A13_A13") (pintype "passive"))
    )
    (net (code "130") (name "unconnected-(J5-PadA14)") (class "Default")
      (node (ref "J5") (pin "A14") (pinfunction "A14_A14") (pintype "passive"))
    )
    (net (code "131") (name "unconnected-(J5-PadB11)") (class "Default")
      (node (ref "J5") (pin "B11") (pinfunction "B11_B11") (pintype "passive"))
    )
    (net (code "132") (name "unconnected-(J5-PadB12)") (class "Default")
      (node (ref "J5") (pin "B12") (pinfunction "B12_B12") (pintype "passive"))
    )
    (net (code "133") (name "unconnected-(J5-PadB13)") (class "Default")
      (node (ref "J5") (pin "B13") (pinfunction "B13_B13") (pintype "passive"))
    )
    (net (code "134") (name "unconnected-(J5-PadB14)") (class "Default")
      (node (ref "J5") (pin "B14") (pinfunction "B14_B14") (pintype "passive"))
    )
  )
)
